# Phare.net
KiCad netlist of a schematic drawn in Altium Designer
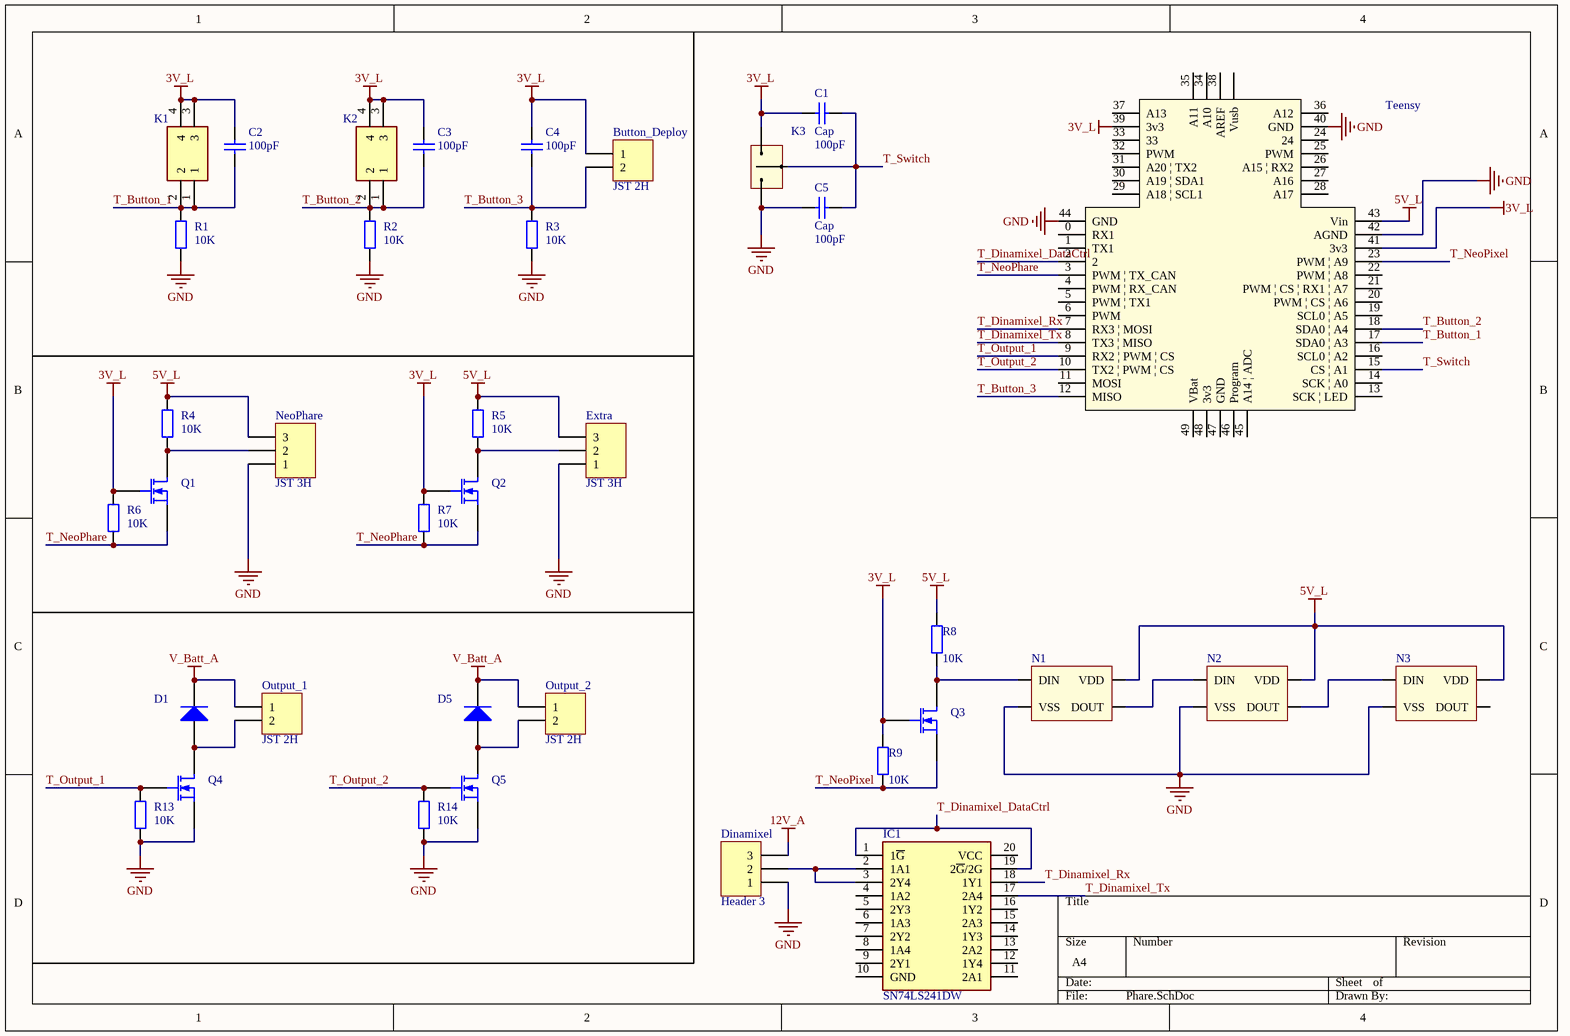
[diagram p0: Phare.SchDoc]

(export (version "E")
  (design (tool "Eeschema 10.0.6"))
  (components
    (comp (ref "Button_Deploy")
      (value "JST 2H")
      (footprint "S2B-XH-A")
      (description "Header, 2-Pin")
      (fields (field (name "PUBLISHER") "Altium Limited"))
      (libsource (lib "Miscellaneous Connectors") (part "Header 2"))
    )
    (comp (ref "C1")
      (value "Cap")
      (footprint "Capacitor 1206")
      (description "Capacitor")
      (fields (field (name "ALTIUM_VALUE") "100pF") (field (name "PUBLISHER") "Altium Limited"))
      (libsource (lib "Miscellaneous Devices") (part "Cap"))
    )
    (comp (ref "C2")
      (value "100pF")
      (footprint "Capacitor 1206")
      (description "Capacitor")
      (fields (field (name "Comment") "Cap") (field (name "PUBLISHER") "Altium Limited"))
      (libsource (lib "Miscellaneous Devices") (part "Cap"))
    )
    (comp (ref "C3")
      (value "100pF")
      (footprint "Capacitor 1206")
      (description "Capacitor")
      (fields (field (name "Comment") "Cap") (field (name "PUBLISHER") "Altium Limited"))
      (libsource (lib "Miscellaneous Devices") (part "Cap"))
    )
    (comp (ref "C4")
      (value "100pF")
      (footprint "Capacitor 1206")
      (description "Capacitor")
      (fields (field (name "Comment") "Cap") (field (name "PUBLISHER") "Altium Limited"))
      (libsource (lib "Miscellaneous Devices") (part "Cap"))
    )
    (comp (ref "C5")
      (value "Cap")
      (footprint "Capacitor 1206")
      (description "Capacitor")
      (fields (field (name "ALTIUM_VALUE") "100pF") (field (name "PUBLISHER") "Altium Limited"))
      (libsource (lib "Miscellaneous Devices") (part "Cap"))
    )
    (comp (ref "D1")
      (value "Diode")
      (footprint "SMC")
      (description "Default Diode")
      (fields (field (name "PUBLISHER") "Altium Limited"))
      (libsource (lib "Miscellaneous Devices") (part "Diode"))
    )
    (comp (ref "D5")
      (value "Diode")
      (footprint "SMC")
      (description "Default Diode")
      (fields (field (name "PUBLISHER") "Altium Limited"))
      (libsource (lib "Miscellaneous Devices") (part "Diode"))
    )
    (comp (ref "Dinamixel")
      (value "Header 3")
      (footprint "Molex SPOX 3x1H")
      (description "Header, 3-Pin")
      (fields (field (name "PUBLISHER") "Altium Limited"))
      (libsource (lib "") (part "Header 3_1"))
    )
    (comp (ref "Extra")
      (value "JST 3H")
      (footprint "S3B-XH-A")
      (description "Header, 3-Pin")
      (fields (field (name "PUBLISHER") "Altium Limited"))
      (libsource (lib "Miscellaneous Connectors") (part "Header 3"))
    )
    (comp (ref "IC1")
      (value "SN74LS241DW")
      (footprint "SOIC127P1030X265-20N")
      (description "Integrated Circuit")
      (fields (field (name "MOUSER PART NUMBER") "595-SN74LS241DW"))
      (libsource (lib "*") (part "SN74LS241DW"))
    )
    (comp (ref "K1")
      (value "4-1437565-1")
      (footprint "SamacSys:FSM-SWITCH")
      (description "Switch")
      (libsource (lib "*") (part "4-1437565-1"))
    )
    (comp (ref "K2")
      (value "4-1437565-1")
      (footprint "SamacSys:FSM-SWITCH")
      (description "Switch")
      (libsource (lib "*") (part "4-1437565-1"))
    )
    (comp (ref "K3")
      (value "Switch")
      (footprint "SWITCH")
      (description "3 pos switch, 09.03290.01")
      (libsource (lib "Robot_2020") (part "Switch"))
    )
    (comp (ref "N1")
      (value "NeoPixel")
      (footprint "Neopixel")
      (libsource (lib "Robot_2020") (part "NeoPixel"))
    )
    (comp (ref "N2")
      (value "NeoPixel")
      (footprint "Neopixel")
      (libsource (lib "Robot_2020") (part "NeoPixel"))
    )
    (comp (ref "N3")
      (value "NeoPixel")
      (footprint "Neopixel")
      (libsource (lib "Robot_2020") (part "NeoPixel"))
    )
    (comp (ref "NeoPhare")
      (value "JST 3H")
      (footprint "S3B-XH-A")
      (description "Header, 3-Pin")
      (fields (field (name "PUBLISHER") "Altium Limited"))
      (libsource (lib "Miscellaneous Connectors") (part "Header 3"))
    )
    (comp (ref "Output_1")
      (value "JST 2H")
      (footprint "S2B-XH-A")
      (description "Header, 2-Pin")
      (fields (field (name "PUBLISHER") "Altium Limited"))
      (libsource (lib "Miscellaneous Connectors") (part "Header 2"))
    )
    (comp (ref "Output_2")
      (value "JST 2H")
      (footprint "S2B-XH-A")
      (description "Header, 2-Pin")
      (fields (field (name "PUBLISHER") "Altium Limited"))
      (libsource (lib "Miscellaneous Connectors") (part "Header 2"))
    )
    (comp (ref "Q1")
      (value "MOSFET-N")
      (footprint "SOT23_M")
      (description "N-Channel MOSFET")
      (fields (field (name "PUBLISHER") "Altium Limited"))
      (libsource (lib "Miscellaneous Devices") (part "MOSFET-N"))
    )
    (comp (ref "Q2")
      (value "MOSFET-N")
      (footprint "SOT23_M")
      (description "N-Channel MOSFET")
      (fields (field (name "PUBLISHER") "Altium Limited"))
      (libsource (lib "Miscellaneous Devices") (part "MOSFET-N"))
    )
    (comp (ref "Q3")
      (value "MOSFET-N")
      (footprint "SOT23_M")
      (description "N-Channel MOSFET")
      (fields (field (name "PUBLISHER") "Altium Limited"))
      (libsource (lib "Miscellaneous Devices") (part "MOSFET-N"))
    )
    (comp (ref "Q4")
      (value "MOSFET-N")
      (footprint "SOT23_M")
      (description "N-Channel MOSFET")
      (fields (field (name "PUBLISHER") "Altium Limited"))
      (libsource (lib "Miscellaneous Devices") (part "MOSFET-N"))
    )
    (comp (ref "Q5")
      (value "MOSFET-N")
      (footprint "SOT23_M")
      (description "N-Channel MOSFET")
      (fields (field (name "PUBLISHER") "Altium Limited"))
      (libsource (lib "Miscellaneous Devices") (part "MOSFET-N"))
    )
    (comp (ref "R1")
      (value "10K")
      (footprint "Resistor 1206")
      (description "Resistor")
      (fields (field (name "Comment") "Res2") (field (name "PUBLISHER") "Altium Limited"))
      (libsource (lib "Miscellaneous Devices") (part "Res2"))
    )
    (comp (ref "R2")
      (value "10K")
      (footprint "Resistor 1206")
      (description "Resistor")
      (fields (field (name "Comment") "Res2") (field (name "PUBLISHER") "Altium Limited"))
      (libsource (lib "Miscellaneous Devices") (part "Res2"))
    )
    (comp (ref "R3")
      (value "10K")
      (footprint "Resistor 1206")
      (description "Resistor")
      (fields (field (name "Comment") "Res2") (field (name "PUBLISHER") "Altium Limited"))
      (libsource (lib "Miscellaneous Devices") (part "Res2"))
    )
    (comp (ref "R4")
      (value "10K")
      (footprint "Resistor 1206")
      (description "Resistor")
      (fields (field (name "Comment") "Res2") (field (name "PUBLISHER") "Altium Limited"))
      (libsource (lib "Miscellaneous Devices") (part "Res2"))
    )
    (comp (ref "R5")
      (value "10K")
      (footprint "Resistor 1206")
      (description "Resistor")
      (fields (field (name "Comment") "Res2") (field (name "PUBLISHER") "Altium Limited"))
      (libsource (lib "Miscellaneous Devices") (part "Res2"))
    )
    (comp (ref "R6")
      (value "10K")
      (footprint "Resistor 1206")
      (description "Resistor")
      (fields (field (name "Comment") "Res2") (field (name "PUBLISHER") "Altium Limited"))
      (libsource (lib "Miscellaneous Devices") (part "Res2"))
    )
    (comp (ref "R7")
      (value "10K")
      (footprint "Resistor 1206")
      (description "Resistor")
      (fields (field (name "Comment") "Res2") (field (name "PUBLISHER") "Altium Limited"))
      (libsource (lib "Miscellaneous Devices") (part "Res2"))
    )
    (comp (ref "R8")
      (value "10K")
      (footprint "Resistor 1206")
      (description "Resistor")
      (fields (field (name "Comment") "Res2") (field (name "PUBLISHER") "Altium Limited"))
      (libsource (lib "Miscellaneous Devices") (part "Res2"))
    )
    (comp (ref "R9")
      (value "10K")
      (footprint "Resistor 1206")
      (description "Resistor")
      (fields (field (name "Comment") "Res2") (field (name "PUBLISHER") "Altium Limited"))
      (libsource (lib "Miscellaneous Devices") (part "Res2"))
    )
    (comp (ref "R13")
      (value "10K")
      (footprint "Resistor 1206")
      (description "Resistor")
      (fields (field (name "Comment") "Res2") (field (name "PUBLISHER") "Altium Limited"))
      (libsource (lib "Miscellaneous Devices") (part "Res2"))
    )
    (comp (ref "R14")
      (value "10K")
      (footprint "Resistor 1206")
      (description "Resistor")
      (fields (field (name "Comment") "Res2") (field (name "PUBLISHER") "Altium Limited"))
      (libsource (lib "Miscellaneous Devices") (part "Res2"))
    )
    (comp (ref "Teensy")
      (value "Teensy 3.2")
      (footprint "teensy")
      (libsource (lib "Robot_2020") (part "teensy3.2"))
    )
  )
  (nets
    (net (code "1") (name "/T_Button_1") (class "Default")
      (node (ref "C2") (pin "2") (pinfunction "2_2") (pintype "passive"))
      (node (ref "K1") (pin "1") (pinfunction "1_1") (pintype "passive"))
      (node (ref "K1") (pin "2") (pinfunction "2_2") (pintype "passive"))
      (node (ref "R1") (pin "1") (pinfunction "1_1") (pintype "passive"))
      (node (ref "Teensy") (pin "17") (pinfunction "SDA0_¦_A3_17") (pintype "passive"))
    )
    (net (code "2") (name "/T_Button_2") (class "Default")
      (node (ref "C3") (pin "2") (pinfunction "2_2") (pintype "passive"))
      (node (ref "K2") (pin "1") (pinfunction "1_1") (pintype "passive"))
      (node (ref "K2") (pin "2") (pinfunction "2_2") (pintype "passive"))
      (node (ref "R2") (pin "1") (pinfunction "1_1") (pintype "passive"))
      (node (ref "Teensy") (pin "18") (pinfunction "SDA0_¦_A4_18") (pintype "passive"))
    )
    (net (code "3") (name "/T_Button_3") (class "Default")
      (node (ref "Button_Deploy") (pin "2") (pinfunction "2_2") (pintype "passive"))
      (node (ref "C4") (pin "2") (pinfunction "2_2") (pintype "passive"))
      (node (ref "R3") (pin "1") (pinfunction "1_1") (pintype "passive"))
      (node (ref "Teensy") (pin "12") (pinfunction "MISO_12") (pintype "passive"))
    )
    (net (code "4") (name "/T_Dinamixel_DataCtrl") (class "Default")
      (node (ref "IC1") (pin "1") (pinfunction "1~{G}_1") (pintype "passive"))
      (node (ref "IC1") (pin "19") (pinfunction "2~{G}/2G_19") (pintype "passive"))
      (node (ref "Teensy") (pin "2") (pinfunction "2_2") (pintype "passive"))
    )
    (net (code "5") (name "/T_Dinamixel_Rx") (class "Default")
      (node (ref "IC1") (pin "18") (pinfunction "1Y1_18") (pintype "passive"))
      (node (ref "Teensy") (pin "7") (pinfunction "RX3_¦_MOSI_7") (pintype "passive"))
    )
    (net (code "6") (name "/T_Dinamixel_Tx") (class "Default")
      (node (ref "IC1") (pin "17") (pinfunction "2A4_17") (pintype "passive"))
      (node (ref "Teensy") (pin "8") (pinfunction "TX3_¦_MISO_8") (pintype "passive"))
    )
    (net (code "7") (name "/T_NeoPhare") (class "Default")
      (node (ref "Q1") (pin "3") (pinfunction "S_3") (pintype "passive"))
      (node (ref "Q2") (pin "3") (pinfunction "S_3") (pintype "passive"))
      (node (ref "R6") (pin "2") (pinfunction "2_2") (pintype "passive"))
      (node (ref "R7") (pin "2") (pinfunction "2_2") (pintype "passive"))
      (node (ref "Teensy") (pin "3") (pinfunction "PWM_¦_TX_CAN_3") (pintype "passive"))
    )
    (net (code "8") (name "/T_NeoPixel") (class "Default")
      (node (ref "Q3") (pin "3") (pinfunction "S_3") (pintype "passive"))
      (node (ref "R9") (pin "2") (pinfunction "2_2") (pintype "passive"))
      (node (ref "Teensy") (pin "23") (pinfunction "PWM_¦_A9_23") (pintype "passive"))
    )
    (net (code "9") (name "/T_Output_1") (class "Default")
      (node (ref "Q4") (pin "2") (pinfunction "G_2") (pintype "passive"))
      (node (ref "R13") (pin "1") (pinfunction "1_1") (pintype "passive"))
      (node (ref "Teensy") (pin "9") (pinfunction "RX2_¦_PWM_¦_CS_9") (pintype "passive"))
    )
    (net (code "10") (name "/T_Output_2") (class "Default")
      (node (ref "Q5") (pin "2") (pinfunction "G_2") (pintype "passive"))
      (node (ref "R14") (pin "1") (pinfunction "1_1") (pintype "passive"))
      (node (ref "Teensy") (pin "10") (pinfunction "TX2_¦_PWM_¦_CS_10") (pintype "passive"))
    )
    (net (code "11") (name "/T_Switch") (class "Default")
      (node (ref "C1") (pin "2") (pinfunction "2_2") (pintype "passive"))
      (node (ref "C5") (pin "2") (pinfunction "2_2") (pintype "passive"))
      (node (ref "K3") (pin "1") (pinfunction "M_1") (pintype "passive"))
      (node (ref "Teensy") (pin "15") (pinfunction "CS_¦_A1_15") (pintype "passive"))
    )
    (net (code "12") (name "3V_L") (class "Default")
      (node (ref "Button_Deploy") (pin "1") (pinfunction "1_1") (pintype "passive"))
      (node (ref "C1") (pin "1") (pinfunction "1_1") (pintype "passive"))
      (node (ref "C2") (pin "1") (pinfunction "1_1") (pintype "passive"))
      (node (ref "C3") (pin "1") (pinfunction "1_1") (pintype "passive"))
      (node (ref "C4") (pin "1") (pinfunction "1_1") (pintype "passive"))
      (node (ref "K1") (pin "3") (pinfunction "3_3") (pintype "passive"))
      (node (ref "K1") (pin "4") (pinfunction "4_4") (pintype "passive"))
      (node (ref "K2") (pin "3") (pinfunction "3_3") (pintype "passive"))
      (node (ref "K2") (pin "4") (pinfunction "4_4") (pintype "passive"))
      (node (ref "K3") (pin "0") (pinfunction "L_0") (pintype "passive"))
      (node (ref "Q1") (pin "2") (pinfunction "G_2") (pintype "passive"))
      (node (ref "Q2") (pin "2") (pinfunction "G_2") (pintype "passive"))
      (node (ref "Q3") (pin "2") (pinfunction "G_2") (pintype "passive"))
      (node (ref "R6") (pin "1") (pinfunction "1_1") (pintype "passive"))
      (node (ref "R7") (pin "1") (pinfunction "1_1") (pintype "passive"))
      (node (ref "R9") (pin "1") (pinfunction "1_1") (pintype "passive"))
      (node (ref "Teensy") (pin "39") (pinfunction "3v3_39") (pintype "passive"))
      (node (ref "Teensy") (pin "41") (pinfunction "3v3_41") (pintype "passive"))
    )
    (net (code "13") (name "5V_L") (class "Default")
      (node (ref "Extra") (pin "3") (pinfunction "3_3") (pintype "passive"))
      (node (ref "N1") (pin "4") (pinfunction "VDD_4") (pintype "passive"))
      (node (ref "N2") (pin "4") (pinfunction "VDD_4") (pintype "passive"))
      (node (ref "N3") (pin "4") (pinfunction "VDD_4") (pintype "passive"))
      (node (ref "NeoPhare") (pin "3") (pinfunction "3_3") (pintype "passive"))
      (node (ref "R4") (pin "1") (pinfunction "1_1") (pintype "passive"))
      (node (ref "R5") (pin "1") (pinfunction "1_1") (pintype "passive"))
      (node (ref "R8") (pin "1") (pinfunction "1_1") (pintype "passive"))
      (node (ref "Teensy") (pin "43") (pinfunction "Vin_43") (pintype "passive"))
    )
    (net (code "14") (name "12V_A") (class "Default")
      (node (ref "Dinamixel") (pin "3") (pinfunction "3_3") (pintype "passive"))
    )
    (net (code "15") (name "GND") (class "Default")
      (node (ref "C5") (pin "1") (pinfunction "1_1") (pintype "passive"))
      (node (ref "Dinamixel") (pin "1") (pinfunction "1_1") (pintype "passive"))
      (node (ref "Extra") (pin "1") (pinfunction "1_1") (pintype "passive"))
      (node (ref "K3") (pin "2") (pinfunction "R_2") (pintype "passive"))
      (node (ref "N1") (pin "2") (pinfunction "VSS_2") (pintype "passive"))
      (node (ref "N2") (pin "2") (pinfunction "VSS_2") (pintype "passive"))
      (node (ref "N3") (pin "2") (pinfunction "VSS_2") (pintype "passive"))
      (node (ref "NeoPhare") (pin "1") (pinfunction "1_1") (pintype "passive"))
      (node (ref "Q4") (pin "3") (pinfunction "S_3") (pintype "passive"))
      (node (ref "Q5") (pin "3") (pinfunction "S_3") (pintype "passive"))
      (node (ref "R1") (pin "2") (pinfunction "2_2") (pintype "passive"))
      (node (ref "R13") (pin "2") (pinfunction "2_2") (pintype "passive"))
      (node (ref "R14") (pin "2") (pinfunction "2_2") (pintype "passive"))
      (node (ref "R2") (pin "2") (pinfunction "2_2") (pintype "passive"))
      (node (ref "R3") (pin "2") (pinfunction "2_2") (pintype "passive"))
      (node (ref "Teensy") (pin "40") (pinfunction "GND_40") (pintype "passive"))
      (node (ref "Teensy") (pin "42") (pinfunction "AGND_42") (pintype "passive"))
      (node (ref "Teensy") (pin "44") (pinfunction "GND_44") (pintype "passive"))
    )
    (net (code "16") (name "Net-(D1-A)") (class "Default")
      (node (ref "D1") (pin "1") (pinfunction "A_1") (pintype "passive"))
      (node (ref "Output_1") (pin "2") (pinfunction "2_2") (pintype "passive"))
      (node (ref "Q4") (pin "1") (pinfunction "D_1") (pintype "passive"))
    )
    (net (code "17") (name "Net-(D5-A)") (class "Default")
      (node (ref "D5") (pin "1") (pinfunction "A_1") (pintype "passive"))
      (node (ref "Output_2") (pin "2") (pinfunction "2_2") (pintype "passive"))
      (node (ref "Q5") (pin "1") (pinfunction "D_1") (pintype "passive"))
    )
    (net (code "18") (name "Net-(IC1-1A1)") (class "Default")
      (node (ref "Dinamixel") (pin "2") (pinfunction "2_2") (pintype "passive"))
      (node (ref "IC1") (pin "2") (pinfunction "1A1_2") (pintype "passive"))
      (node (ref "IC1") (pin "3") (pinfunction "2Y4_3") (pintype "passive"))
    )
    (net (code "19") (name "Net-(N1-DIN)") (class "Default")
      (node (ref "N1") (pin "3") (pinfunction "DIN_3") (pintype "passive"))
      (node (ref "Q3") (pin "1") (pinfunction "D_1") (pintype "passive"))
      (node (ref "R8") (pin "2") (pinfunction "2_2") (pintype "passive"))
    )
    (net (code "20") (name "Net-(N1-DOUT)") (class "Default")
      (node (ref "N1") (pin "1") (pinfunction "DOUT_1") (pintype "passive"))
      (node (ref "N2") (pin "3") (pinfunction "DIN_3") (pintype "passive"))
    )
    (net (code "21") (name "Net-(N2-DOUT)") (class "Default")
      (node (ref "N2") (pin "1") (pinfunction "DOUT_1") (pintype "passive"))
      (node (ref "N3") (pin "3") (pinfunction "DIN_3") (pintype "passive"))
    )
    (net (code "22") (name "Net-(Q1-D)") (class "Default")
      (node (ref "NeoPhare") (pin "2") (pinfunction "2_2") (pintype "passive"))
      (node (ref "Q1") (pin "1") (pinfunction "D_1") (pintype "passive"))
      (node (ref "R4") (pin "2") (pinfunction "2_2") (pintype "passive"))
    )
    (net (code "23") (name "Net-(Q2-D)") (class "Default")
      (node (ref "Extra") (pin "2") (pinfunction "2_2") (pintype "passive"))
      (node (ref "Q2") (pin "1") (pinfunction "D_1") (pintype "passive"))
      (node (ref "R5") (pin "2") (pinfunction "2_2") (pintype "passive"))
    )
    (net (code "24") (name "V_Batt_A") (class "Default")
      (node (ref "D1") (pin "2") (pinfunction "K_2") (pintype "passive"))
      (node (ref "D5") (pin "2") (pinfunction "K_2") (pintype "passive"))
      (node (ref "Output_1") (pin "1") (pinfunction "1_1") (pintype "passive"))
      (node (ref "Output_2") (pin "1") (pinfunction "1_1") (pintype "passive"))
    )
    (net (code "25") (name "unconnected-(IC1-1A2-Pad4)") (class "Default")
      (node (ref "IC1") (pin "4") (pinfunction "1A2_4") (pintype "passive"))
    )
    (net (code "26") (name "unconnected-(IC1-1A3-Pad6)") (class "Default")
      (node (ref "IC1") (pin "6") (pinfunction "1A3_6") (pintype "passive"))
    )
    (net (code "27") (name "unconnected-(IC1-1A4-Pad8)") (class "Default")
      (node (ref "IC1") (pin "8") (pinfunction "1A4_8") (pintype "passive"))
    )
    (net (code "28") (name "unconnected-(IC1-1Y2-Pad16)") (class "Default")
      (node (ref "IC1") (pin "16") (pinfunction "1Y2_16") (pintype "passive"))
    )
    (net (code "29") (name "unconnected-(IC1-1Y3-Pad14)") (class "Default")
      (node (ref "IC1") (pin "14") (pinfunction "1Y3_14") (pintype "passive"))
    )
    (net (code "30") (name "unconnected-(IC1-1Y4-Pad12)") (class "Default")
      (node (ref "IC1") (pin "12") (pinfunction "1Y4_12") (pintype "passive"))
    )
    (net (code "31") (name "unconnected-(IC1-2A1-Pad11)") (class "Default")
      (node (ref "IC1") (pin "11") (pinfunction "2A1_11") (pintype "passive"))
    )
    (net (code "32") (name "unconnected-(IC1-2A2-Pad13)") (class "Default")
      (node (ref "IC1") (pin "13") (pinfunction "2A2_13") (pintype "passive"))
    )
    (net (code "33") (name "unconnected-(IC1-2A3-Pad15)") (class "Default")
      (node (ref "IC1") (pin "15") (pinfunction "2A3_15") (pintype "passive"))
    )
    (net (code "34") (name "unconnected-(IC1-2Y1-Pad9)") (class "Default")
      (node (ref "IC1") (pin "9") (pinfunction "2Y1_9") (pintype "passive"))
    )
    (net (code "35") (name "unconnected-(IC1-2Y2-Pad7)") (class "Default")
      (node (ref "IC1") (pin "7") (pinfunction "2Y2_7") (pintype "passive"))
    )
    (net (code "36") (name "unconnected-(IC1-2Y3-Pad5)") (class "Default")
      (node (ref "IC1") (pin "5") (pinfunction "2Y3_5") (pintype "passive"))
    )
    (net (code "37") (name "unconnected-(IC1-GND-Pad10)") (class "Default")
      (node (ref "IC1") (pin "10") (pinfunction "GND_10") (pintype "passive"))
    )
    (net (code "38") (name "unconnected-(IC1-VCC-Pad20)") (class "Default")
      (node (ref "IC1") (pin "20") (pinfunction "VCC_20") (pintype "passive"))
    )
    (net (code "39") (name "unconnected-(N3-DOUT-Pad1)") (class "Default")
      (node (ref "N3") (pin "1") (pinfunction "DOUT_1") (pintype "passive"))
    )
    (net (code "40") (name "unconnected-(Teensy-3v3-Pad48)") (class "Default")
      (node (ref "Teensy") (pin "48") (pinfunction "3v3_48") (pintype "passive"))
    )
    (net (code "41") (name "unconnected-(Teensy-A10-Pad34)") (class "Default")
      (node (ref "Teensy") (pin "34") (pinfunction "A10_34") (pintype "passive"))
    )
    (net (code "42") (name "unconnected-(Teensy-A11-Pad35)") (class "Default")
      (node (ref "Teensy") (pin "35") (pinfunction "A11_35") (pintype "passive"))
    )
    (net (code "43") (name "unconnected-(Teensy-A12-Pad36)") (class "Default")
      (node (ref "Teensy") (pin "36") (pinfunction "A12_36") (pintype "passive"))
    )
    (net (code "44") (name "unconnected-(Teensy-A13-Pad37)") (class "Default")
      (node (ref "Teensy") (pin "37") (pinfunction "A13_37") (pintype "passive"))
    )
    (net (code "45") (name "unconnected-(Teensy-A14_¦_ADC-Pad45)") (class "Default")
      (node (ref "Teensy") (pin "45") (pinfunction "A14_¦_ADC_45") (pintype "passive"))
    )
    (net (code "46") (name "unconnected-(Teensy-A15_¦_RX2-Pad26)") (class "Default")
      (node (ref "Teensy") (pin "26") (pinfunction "A15_¦_RX2_26") (pintype "passive"))
    )
    (net (code "47") (name "unconnected-(Teensy-A16-Pad27)") (class "Default")
      (node (ref "Teensy") (pin "27") (pinfunction "A16_27") (pintype "passive"))
    )
    (net (code "48") (name "unconnected-(Teensy-A17-Pad28)") (class "Default")
      (node (ref "Teensy") (pin "28") (pinfunction "A17_28") (pintype "passive"))
    )
    (net (code "49") (name "unconnected-(Teensy-A18_¦_SCL1-Pad29)") (class "Default")
      (node (ref "Teensy") (pin "29") (pinfunction "A18_¦_SCL1_29") (pintype "passive"))
    )
    (net (code "50") (name "unconnected-(Teensy-A19_¦_SDA1-Pad30)") (class "Default")
      (node (ref "Teensy") (pin "30") (pinfunction "A19_¦_SDA1_30") (pintype "passive"))
    )
    (net (code "51") (name "unconnected-(Teensy-A20_¦_TX2-Pad31)") (class "Default")
      (node (ref "Teensy") (pin "31") (pinfunction "A20_¦_TX2_31") (pintype "passive"))
    )
    (net (code "52") (name "unconnected-(Teensy-AREF-Pad38)") (class "Default")
      (node (ref "Teensy") (pin "38") (pinfunction "AREF_38") (pintype "passive"))
    )
    (net (code "53") (name "unconnected-(Teensy-GND-Pad47)") (class "Default")
      (node (ref "Teensy") (pin "47") (pinfunction "GND_47") (pintype "passive"))
    )
    (net (code "54") (name "unconnected-(Teensy-MOSI-Pad11)") (class "Default")
      (node (ref "Teensy") (pin "11") (pinfunction "MOSI_11") (pintype "passive"))
    )
    (net (code "55") (name "unconnected-(Teensy-PWM-Pad6)") (class "Default")
      (node (ref "Teensy") (pin "6") (pinfunction "PWM_6") (pintype "passive"))
    )
    (net (code "56") (name "unconnected-(Teensy-PWM-Pad25)") (class "Default")
      (node (ref "Teensy") (pin "25") (pinfunction "PWM_25") (pintype "passive"))
    )
    (net (code "57") (name "unconnected-(Teensy-PWM-Pad32)") (class "Default")
      (node (ref "Teensy") (pin "32") (pinfunction "PWM_32") (pintype "passive"))
    )
    (net (code "58") (name "unconnected-(Teensy-PWM_¦_A8-Pad22)") (class "Default")
      (node (ref "Teensy") (pin "22") (pinfunction "PWM_¦_A8_22") (pintype "passive"))
    )
    (net (code "59") (name "unconnected-(Teensy-PWM_¦_CS_¦_A6-Pad20)") (class "Default")
      (node (ref "Teensy") (pin "20") (pinfunction "PWM_¦_CS_¦_A6_20") (pintype "passive"))
    )
    (net (code "60") (name "unconnected-(Teensy-PWM_¦_CS_¦_RX1_¦_A7-Pad21)") (class "Default")
      (node (ref "Teensy") (pin "21") (pinfunction "PWM_¦_CS_¦_RX1_¦_A7_21") (pintype "passive"))
    )
    (net (code "61") (name "unconnected-(Teensy-PWM_¦_RX_CAN-Pad4)") (class "Default")
      (node (ref "Teensy") (pin "4") (pinfunction "PWM_¦_RX_CAN_4") (pintype "passive"))
    )
    (net (code "62") (name "unconnected-(Teensy-PWM_¦_TX1-Pad5)") (class "Default")
      (node (ref "Teensy") (pin "5") (pinfunction "PWM_¦_TX1_5") (pintype "passive"))
    )
    (net (code "63") (name "unconnected-(Teensy-Pad24)") (class "Default")
      (node (ref "Teensy") (pin "24") (pinfunction "24_24") (pintype "passive"))
    )
    (net (code "64") (name "unconnected-(Teensy-Pad33)") (class "Default")
      (node (ref "Teensy") (pin "33") (pinfunction "33_33") (pintype "passive"))
    )
    (net (code "65") (name "unconnected-(Teensy-Program-Pad46)") (class "Default")
      (node (ref "Teensy") (pin "46") (pinfunction "Program_46") (pintype "passive"))
    )
    (net (code "66") (name "unconnected-(Teensy-RX1-Pad0)") (class "Default")
      (node (ref "Teensy") (pin "0") (pinfunction "RX1_0") (pintype "passive"))
    )
    (net (code "67") (name "unconnected-(Teensy-SCK_¦_A0-Pad14)") (class "Default")
      (node (ref "Teensy") (pin "14") (pinfunction "SCK_¦_A0_14") (pintype "passive"))
    )
    (net (code "68") (name "unconnected-(Teensy-SCK_¦_LED-Pad13)") (class "Default")
      (node (ref "Teensy") (pin "13") (pinfunction "SCK_¦_LED_13") (pintype "passive"))
    )
    (net (code "69") (name "unconnected-(Teensy-SCL0_¦_A2-Pad16)") (class "Default")
      (node (ref "Teensy") (pin "16") (pinfunction "SCL0_¦_A2_16") (pintype "passive"))
    )
    (net (code "70") (name "unconnected-(Teensy-SCL0_¦_A5-Pad19)") (class "Default")
      (node (ref "Teensy") (pin "19") (pinfunction "SCL0_¦_A5_19") (pintype "passive"))
    )
    (net (code "71") (name "unconnected-(Teensy-TX1-Pad1)") (class "Default")
      (node (ref "Teensy") (pin "1") (pinfunction "TX1_1") (pintype "passive"))
    )
    (net (code "72") (name "unconnected-(Teensy-VBat-Pad49)") (class "Default")
      (node (ref "Teensy") (pin "49") (pinfunction "VBat_49") (pintype "passive"))
    )
    (net (code "73") (name "unconnected-(Teensy-Vusb-Pad50)") (class "Default")
      (node (ref "Teensy") (pin "50") (pinfunction "Vusb_50") (pintype "passive"))
    )
  )
)
